# 07_eMMC.net
KiCad netlist of a schematic drawn in Altium Designer
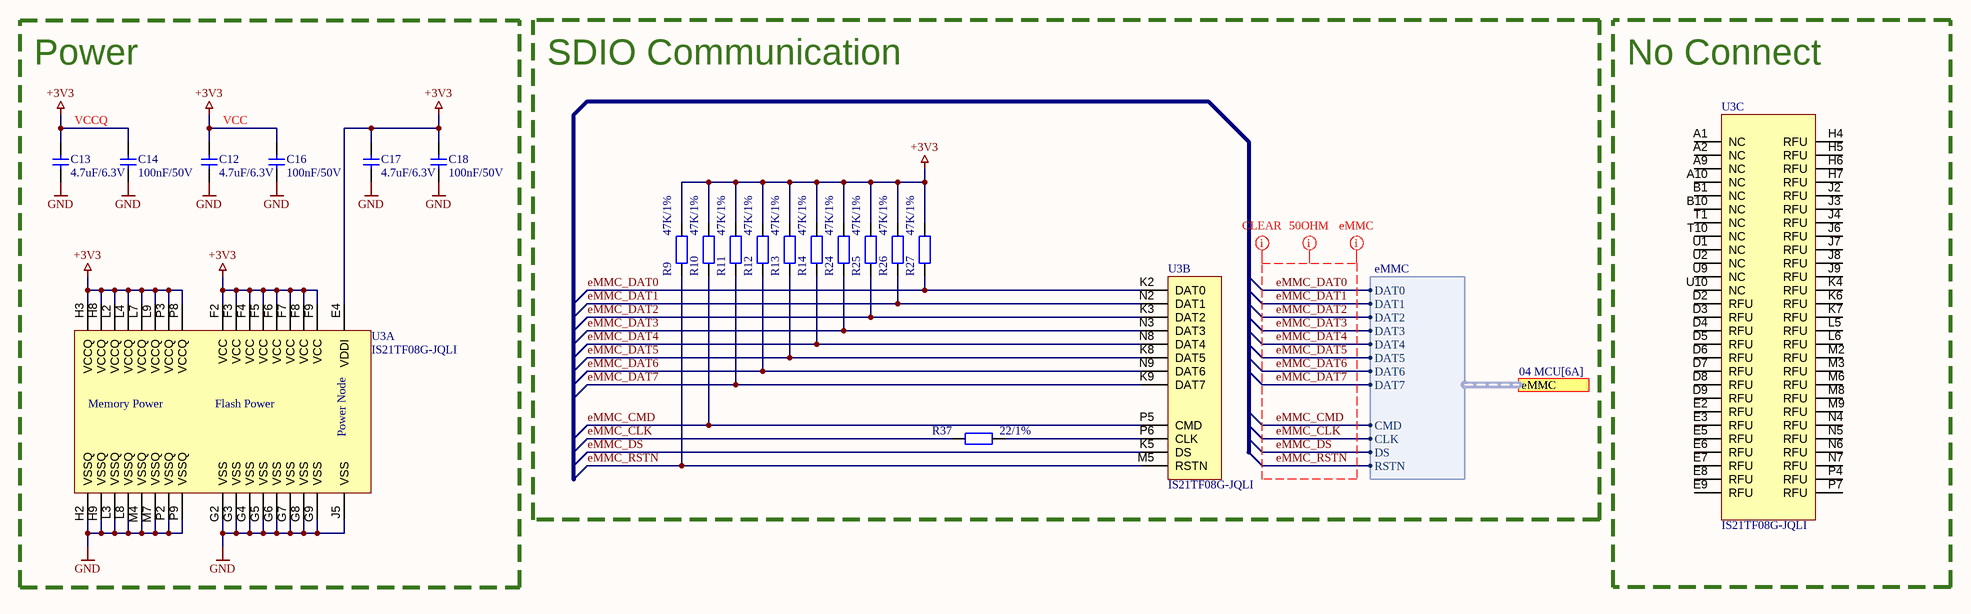
[diagram p0: 07 eMMC.SchDoc]

(export (version "E")
  (design (tool "Eeschema 10.0.6"))
  (components
    (comp (ref "C12")
      (value "4.7uF/6.3V")
      (footprint "CAPC1005X06M-0402")
      (description "4.7 µF ±20% 6.3V Ceramic Capacitor X5R 0402 (1005 Metric)")
      (fields (field (name "MPN") "GRM155R60J475ME47D"))
      (libsource (lib "Symbol") (part "GRM155R60J475ME47D"))
    )
    (comp (ref "C13")
      (value "4.7uF/6.3V")
      (footprint "CAPC1005X06M-0402")
      (description "4.7 µF ±20% 6.3V Ceramic Capacitor X5R 0402 (1005 Metric)")
      (fields (field (name "MPN") "GRM155R60J475ME47D"))
      (libsource (lib "Symbol") (part "GRM155R60J475ME47D"))
    )
    (comp (ref "C14")
      (value "100nF/50V")
      (footprint "CAPC1005X06M-0402")
      (description "0.1 µF ±10% 50V Ceramic Capacitor X7R 0402 (1005 Metric)")
      (fields (field (name "MPN") "GRM155R71H104KE14D"))
      (libsource (lib "Symbol") (part "GRM155R71H104KE14D"))
    )
    (comp (ref "C16")
      (value "100nF/50V")
      (footprint "CAPC1005X06M-0402")
      (description "0.1 µF ±10% 50V Ceramic Capacitor X7R 0402 (1005 Metric)")
      (fields (field (name "MPN") "GRM155R71H104KE14D"))
      (libsource (lib "Symbol") (part "GRM155R71H104KE14D"))
    )
    (comp (ref "C17")
      (value "4.7uF/6.3V")
      (footprint "CAPC1005X06M-0402")
      (description "4.7 µF ±20% 6.3V Ceramic Capacitor X5R 0402 (1005 Metric)")
      (fields (field (name "MPN") "GRM155R60J475ME47D"))
      (libsource (lib "Symbol") (part "GRM155R60J475ME47D"))
    )
    (comp (ref "C18")
      (value "100nF/50V")
      (footprint "CAPC1005X06M-0402")
      (description "0.1 µF ±10% 50V Ceramic Capacitor X7R 0402 (1005 Metric)")
      (fields (field (name "MPN") "GRM155R71H104KE14D"))
      (libsource (lib "Symbol") (part "GRM155R71H104KE14D"))
    )
    (comp (ref "R9")
      (value "47K/1%")
      (footprint "RESC1005X04M-0402")
      (description "47 kOhms ±1% 0.063W, 1/16W Chip Resistor 0402 (1005 Metric) Moisture Resistant Thick Film")
      (fields (field (name "MPN") "RC0402FR-0747KL"))
      (libsource (lib "Symbol") (part "RC0402FR-0747KL"))
    )
    (comp (ref "R10")
      (value "47K/1%")
      (footprint "RESC1005X04M-0402")
      (description "47 kOhms ±1% 0.063W, 1/16W Chip Resistor 0402 (1005 Metric) Moisture Resistant Thick Film")
      (fields (field (name "MPN") "RC0402FR-0747KL"))
      (libsource (lib "Symbol") (part "RC0402FR-0747KL"))
    )
    (comp (ref "R11")
      (value "47K/1%")
      (footprint "RESC1005X04M-0402")
      (description "47 kOhms ±1% 0.063W, 1/16W Chip Resistor 0402 (1005 Metric) Moisture Resistant Thick Film")
      (fields (field (name "MPN") "RC0402FR-0747KL"))
      (libsource (lib "Symbol") (part "RC0402FR-0747KL"))
    )
    (comp (ref "R12")
      (value "47K/1%")
      (footprint "RESC1005X04M-0402")
      (description "47 kOhms ±1% 0.063W, 1/16W Chip Resistor 0402 (1005 Metric) Moisture Resistant Thick Film")
      (fields (field (name "MPN") "RC0402FR-0747KL"))
      (libsource (lib "Symbol") (part "RC0402FR-0747KL"))
    )
    (comp (ref "R13")
      (value "47K/1%")
      (footprint "RESC1005X04M-0402")
      (description "47 kOhms ±1% 0.063W, 1/16W Chip Resistor 0402 (1005 Metric) Moisture Resistant Thick Film")
      (fields (field (name "MPN") "RC0402FR-0747KL"))
      (libsource (lib "Symbol") (part "RC0402FR-0747KL"))
    )
    (comp (ref "R14")
      (value "47K/1%")
      (footprint "RESC1005X04M-0402")
      (description "47 kOhms ±1% 0.063W, 1/16W Chip Resistor 0402 (1005 Metric) Moisture Resistant Thick Film")
      (fields (field (name "MPN") "RC0402FR-0747KL"))
      (libsource (lib "Symbol") (part "RC0402FR-0747KL"))
    )
    (comp (ref "R24")
      (value "47K/1%")
      (footprint "RESC1005X04M-0402")
      (description "47 kOhms ±1% 0.063W, 1/16W Chip Resistor 0402 (1005 Metric) Moisture Resistant Thick Film")
      (fields (field (name "MPN") "RC0402FR-0747KL"))
      (libsource (lib "Symbol") (part "RC0402FR-0747KL"))
    )
    (comp (ref "R25")
      (value "47K/1%")
      (footprint "RESC1005X04M-0402")
      (description "47 kOhms ±1% 0.063W, 1/16W Chip Resistor 0402 (1005 Metric) Moisture Resistant Thick Film")
      (fields (field (name "MPN") "RC0402FR-0747KL"))
      (libsource (lib "Symbol") (part "RC0402FR-0747KL"))
    )
    (comp (ref "R26")
      (value "47K/1%")
      (footprint "RESC1005X04M-0402")
      (description "47 kOhms ±1% 0.063W, 1/16W Chip Resistor 0402 (1005 Metric) Moisture Resistant Thick Film")
      (fields (field (name "MPN") "RC0402FR-0747KL"))
      (libsource (lib "Symbol") (part "RC0402FR-0747KL"))
    )
    (comp (ref "R27")
      (value "47K/1%")
      (footprint "RESC1005X04M-0402")
      (description "47 kOhms ±1% 0.063W, 1/16W Chip Resistor 0402 (1005 Metric) Moisture Resistant Thick Film")
      (fields (field (name "MPN") "RC0402FR-0747KL"))
      (libsource (lib "Symbol") (part "RC0402FR-0747KL"))
    )
    (comp (ref "R37")
      (value "22/1%")
      (footprint "RESC1005X04M-0402")
      (description "22 Ohms ±1% 0.063W, 1/16W Chip Resistor 0402 (1005 Metric) Moisture Resistant Thick Film")
      (fields (field (name "MPN") "RC0402FR-0722RL"))
      (libsource (lib "Symbol") (part "RC0402FR-0722RL"))
    )
    (comp (ref "U3")
      (value "IS21TF08G-JQLI")
      (footprint "BGA180C100P10X18_1400X1400X140")
      (description "FLASH - NAND (TLC) Memory IC 64Gbit MMC 200 MHz 100-LFBGA (14x18)")
      (libsource (lib "Symbol") (part "IS21TF08G-JQLI"))
    )
  )
  (nets
    (net (code "2") (name "+3V3") (class "Default")
      (node (ref "C12") (pin "2") (pinfunction "2_2") (pintype "passive"))
      (node (ref "C13") (pin "2") (pinfunction "2_2") (pintype "passive"))
      (node (ref "C14") (pin "2") (pinfunction "2_2") (pintype "passive"))
      (node (ref "C16") (pin "2") (pinfunction "2_2") (pintype "passive"))
      (node (ref "C17") (pin "2") (pinfunction "2_2") (pintype "passive"))
      (node (ref "C18") (pin "2") (pinfunction "2_2") (pintype "passive"))
      (node (ref "R10") (pin "2") (pinfunction "2_2") (pintype "passive"))
      (node (ref "R11") (pin "2") (pinfunction "2_2") (pintype "passive"))
      (node (ref "R12") (pin "2") (pinfunction "2_2") (pintype "passive"))
      (node (ref "R13") (pin "2") (pinfunction "2_2") (pintype "passive"))
      (node (ref "R14") (pin "2") (pinfunction "2_2") (pintype "passive"))
      (node (ref "R24") (pin "2") (pinfunction "2_2") (pintype "passive"))
      (node (ref "R25") (pin "2") (pinfunction "2_2") (pintype "passive"))
      (node (ref "R26") (pin "2") (pinfunction "2_2") (pintype "passive"))
      (node (ref "R27") (pin "2") (pinfunction "2_2") (pintype "passive"))
      (node (ref "R9") (pin "2") (pinfunction "2_2") (pintype "passive"))
      (node (ref "U3") (pin "E4") (pinfunction "VDDI_E4") (pintype "power_in"))
      (node (ref "U3") (pin "F2") (pinfunction "VCC_F2") (pintype "power_in"))
      (node (ref "U3") (pin "F3") (pinfunction "VCC_F3") (pintype "power_in"))
      (node (ref "U3") (pin "F4") (pinfunction "VCC_F4") (pintype "power_in"))
      (node (ref "U3") (pin "F5") (pinfunction "VCC_F5") (pintype "power_in"))
      (node (ref "U3") (pin "F6") (pinfunction "VCC_F6") (pintype "power_in"))
      (node (ref "U3") (pin "F7") (pinfunction "VCC_F7") (pintype "power_in"))
      (node (ref "U3") (pin "F8") (pinfunction "VCC_F8") (pintype "power_in"))
      (node (ref "U3") (pin "F9") (pinfunction "VCC_F9") (pintype "power_in"))
      (node (ref "U3") (pin "H3") (pinfunction "VCCQ_H3") (pintype "power_in"))
      (node (ref "U3") (pin "H8") (pinfunction "VCCQ_H8") (pintype "power_in"))
      (node (ref "U3") (pin "L2") (pinfunction "VCCQ_L2") (pintype "power_in"))
      (node (ref "U3") (pin "L4") (pinfunction "VCCQ_L4") (pintype "power_in"))
      (node (ref "U3") (pin "L7") (pinfunction "VCCQ_L7") (pintype "power_in"))
      (node (ref "U3") (pin "L9") (pinfunction "VCCQ_L9") (pintype "power_in"))
      (node (ref "U3") (pin "P3") (pinfunction "VCCQ_P3") (pintype "power_in"))
      (node (ref "U3") (pin "P8") (pinfunction "VCCQ_P8") (pintype "power_in"))
    )
    (net (code "3") (name "/eMMC_CLK") (class "Default")
      (node (ref "R37") (pin "1") (pinfunction "1_1") (pintype "passive"))
    )
    (net (code "4") (name "/eMMC_CMD") (class "Default")
      (node (ref "R10") (pin "1") (pinfunction "1_1") (pintype "passive"))
      (node (ref "U3") (pin "P5") (pinfunction "CMD_P5") (pintype "passive"))
    )
    (net (code "5") (name "/eMMC_DAT0") (class "Default")
      (node (ref "R27") (pin "1") (pinfunction "1_1") (pintype "passive"))
      (node (ref "U3") (pin "K2") (pinfunction "DAT0_K2") (pintype "passive"))
    )
    (net (code "6") (name "/eMMC_DAT1") (class "Default")
      (node (ref "R26") (pin "1") (pinfunction "1_1") (pintype "passive"))
      (node (ref "U3") (pin "N2") (pinfunction "DAT1_N2") (pintype "passive"))
    )
    (net (code "7") (name "/eMMC_DAT2") (class "Default")
      (node (ref "R25") (pin "1") (pinfunction "1_1") (pintype "passive"))
      (node (ref "U3") (pin "K3") (pinfunction "DAT2_K3") (pintype "passive"))
    )
    (net (code "8") (name "/eMMC_DAT3") (class "Default")
      (node (ref "R24") (pin "1") (pinfunction "1_1") (pintype "passive"))
      (node (ref "U3") (pin "N3") (pinfunction "DAT3_N3") (pintype "passive"))
    )
    (net (code "9") (name "/eMMC_DAT4") (class "Default")
      (node (ref "R14") (pin "1") (pinfunction "1_1") (pintype "passive"))
      (node (ref "U3") (pin "N8") (pinfunction "DAT4_N8") (pintype "passive"))
    )
    (net (code "10") (name "/eMMC_DAT5") (class "Default")
      (node (ref "R13") (pin "1") (pinfunction "1_1") (pintype "passive"))
      (node (ref "U3") (pin "K8") (pinfunction "DAT5_K8") (pintype "passive"))
    )
    (net (code "11") (name "/eMMC_DAT6") (class "Default")
      (node (ref "R12") (pin "1") (pinfunction "1_1") (pintype "passive"))
      (node (ref "U3") (pin "N9") (pinfunction "DAT6_N9") (pintype "passive"))
    )
    (net (code "12") (name "/eMMC_DAT7") (class "Default")
      (node (ref "R11") (pin "1") (pinfunction "1_1") (pintype "passive"))
      (node (ref "U3") (pin "K9") (pinfunction "DAT7_K9") (pintype "passive"))
    )
    (net (code "13") (name "/eMMC_DS") (class "Default")
      (node (ref "U3") (pin "K5") (pinfunction "DS_K5") (pintype "passive"))
    )
    (net (code "14") (name "/eMMC_RSTN") (class "Default")
      (node (ref "R9") (pin "1") (pinfunction "1_1") (pintype "passive"))
      (node (ref "U3") (pin "M5") (pinfunction "RSTN_M5") (pintype "passive"))
    )
    (net (code "16") (name "GND") (class "Default")
      (node (ref "C12") (pin "1") (pinfunction "1_1") (pintype "passive"))
      (node (ref "C13") (pin "1") (pinfunction "1_1") (pintype "passive"))
      (node (ref "C14") (pin "1") (pinfunction "1_1") (pintype "passive"))
      (node (ref "C16") (pin "1") (pinfunction "1_1") (pintype "passive"))
      (node (ref "C17") (pin "1") (pinfunction "1_1") (pintype "passive"))
      (node (ref "C18") (pin "1") (pinfunction "1_1") (pintype "passive"))
      (node (ref "U3") (pin "G2") (pinfunction "VSS_G2") (pintype "power_in"))
      (node (ref "U3") (pin "G3") (pinfunction "VSS_G3") (pintype "power_in"))
      (node (ref "U3") (pin "G4") (pinfunction "VSS_G4") (pintype "power_in"))
      (node (ref "U3") (pin "G5") (pinfunction "VSS_G5") (pintype "power_in"))
      (node (ref "U3") (pin "G6") (pinfunction "VSS_G6") (pintype "power_in"))
      (node (ref "U3") (pin "G7") (pinfunction "VSS_G7") (pintype "power_in"))
      (node (ref "U3") (pin "G8") (pinfunction "VSS_G8") (pintype "power_in"))
      (node (ref "U3") (pin "G9") (pinfunction "VSS_G9") (pintype "power_in"))
      (node (ref "U3") (pin "H2") (pinfunction "VSSQ_H2") (pintype "power_in"))
      (node (ref "U3") (pin "H9") (pinfunction "VSSQ_H9") (pintype "power_in"))
      (node (ref "U3") (pin "J5") (pinfunction "VSS_J5") (pintype "power_in"))
      (node (ref "U3") (pin "L3") (pinfunction "VSSQ_L3") (pintype "power_in"))
      (node (ref "U3") (pin "L8") (pinfunction "VSSQ_L8") (pintype "power_in"))
      (node (ref "U3") (pin "M4") (pinfunction "VSSQ_M4") (pintype "power_in"))
      (node (ref "U3") (pin "M7") (pinfunction "VSSQ_M7") (pintype "power_in"))
      (node (ref "U3") (pin "P2") (pinfunction "VSSQ_P2") (pintype "power_in"))
      (node (ref "U3") (pin "P9") (pinfunction "VSSQ_P9") (pintype "power_in"))
    )
    (net (code "17") (name "Net-(U3B-CLK)") (class "Default")
      (node (ref "R37") (pin "2") (pinfunction "2_2") (pintype "passive"))
      (node (ref "U3") (pin "P6") (pinfunction "CLK_P6") (pintype "passive"))
    )
    (net (code "18") (name "unconnected-(U3C-NC-PadA1)") (class "Default")
      (node (ref "U3") (pin "A1") (pinfunction "NC_A1") (pintype "passive"))
    )
    (net (code "19") (name "unconnected-(U3C-NC-PadA2)") (class "Default")
      (node (ref "U3") (pin "A2") (pinfunction "NC_A2") (pintype "passive"))
    )
    (net (code "20") (name "unconnected-(U3C-NC-PadA9)") (class "Default")
      (node (ref "U3") (pin "A9") (pinfunction "NC_A9") (pintype "passive"))
    )
    (net (code "21") (name "unconnected-(U3C-NC-PadA10)") (class "Default")
      (node (ref "U3") (pin "A10") (pinfunction "NC_A10") (pintype "passive"))
    )
    (net (code "22") (name "unconnected-(U3C-NC-PadB1)") (class "Default")
      (node (ref "U3") (pin "B1") (pinfunction "NC_B1") (pintype "passive"))
    )
    (net (code "23") (name "unconnected-(U3C-NC-PadB10)") (class "Default")
      (node (ref "U3") (pin "B10") (pinfunction "NC_B10") (pintype "passive"))
    )
    (net (code "24") (name "unconnected-(U3C-NC-PadT1)") (class "Default")
      (node (ref "U3") (pin "T1") (pinfunction "NC_T1") (pintype "passive"))
    )
    (net (code "25") (name "unconnected-(U3C-NC-PadT10)") (class "Default")
      (node (ref "U3") (pin "T10") (pinfunction "NC_T10") (pintype "passive"))
    )
    (net (code "26") (name "unconnected-(U3C-NC-PadU1)") (class "Default")
      (node (ref "U3") (pin "U1") (pinfunction "NC_U1") (pintype "passive"))
    )
    (net (code "27") (name "unconnected-(U3C-NC-PadU2)") (class "Default")
      (node (ref "U3") (pin "U2") (pinfunction "NC_U2") (pintype "passive"))
    )
    (net (code "28") (name "unconnected-(U3C-NC-PadU9)") (class "Default")
      (node (ref "U3") (pin "U9") (pinfunction "NC_U9") (pintype "passive"))
    )
    (net (code "29") (name "unconnected-(U3C-NC-PadU10)") (class "Default")
      (node (ref "U3") (pin "U10") (pinfunction "NC_U10") (pintype "passive"))
    )
    (net (code "30") (name "unconnected-(U3C-RFU-PadD2)") (class "Default")
      (node (ref "U3") (pin "D2") (pinfunction "RFU_D2") (pintype "passive"))
    )
    (net (code "31") (name "unconnected-(U3C-RFU-PadD3)") (class "Default")
      (node (ref "U3") (pin "D3") (pinfunction "RFU_D3") (pintype "passive"))
    )
    (net (code "32") (name "unconnected-(U3C-RFU-PadD4)") (class "Default")
      (node (ref "U3") (pin "D4") (pinfunction "RFU_D4") (pintype "passive"))
    )
    (net (code "33") (name "unconnected-(U3C-RFU-PadD5)") (class "Default")
      (node (ref "U3") (pin "D5") (pinfunction "RFU_D5") (pintype "passive"))
    )
    (net (code "34") (name "unconnected-(U3C-RFU-PadD6)") (class "Default")
      (node (ref "U3") (pin "D6") (pinfunction "RFU_D6") (pintype "passive"))
    )
    (net (code "35") (name "unconnected-(U3C-RFU-PadD7)") (class "Default")
      (node (ref "U3") (pin "D7") (pinfunction "RFU_D7") (pintype "passive"))
    )
    (net (code "36") (name "unconnected-(U3C-RFU-PadD8)") (class "Default")
      (node (ref "U3") (pin "D8") (pinfunction "RFU_D8") (pintype "passive"))
    )
    (net (code "37") (name "unconnected-(U3C-RFU-PadD9)") (class "Default")
      (node (ref "U3") (pin "D9") (pinfunction "RFU_D9") (pintype "passive"))
    )
    (net (code "38") (name "unconnected-(U3C-RFU-PadE2)") (class "Default")
      (node (ref "U3") (pin "E2") (pinfunction "RFU_E2") (pintype "passive"))
    )
    (net (code "39") (name "unconnected-(U3C-RFU-PadE3)") (class "Default")
      (node (ref "U3") (pin "E3") (pinfunction "RFU_E3") (pintype "passive"))
    )
    (net (code "40") (name "unconnected-(U3C-RFU-PadE5)") (class "Default")
      (node (ref "U3") (pin "E5") (pinfunction "RFU_E5") (pintype "passive"))
    )
    (net (code "41") (name "unconnected-(U3C-RFU-PadE6)") (class "Default")
      (node (ref "U3") (pin "E6") (pinfunction "RFU_E6") (pintype "passive"))
    )
    (net (code "42") (name "unconnected-(U3C-RFU-PadE7)") (class "Default")
      (node (ref "U3") (pin "E7") (pinfunction "RFU_E7") (pintype "passive"))
    )
    (net (code "43") (name "unconnected-(U3C-RFU-PadE8)") (class "Default")
      (node (ref "U3") (pin "E8") (pinfunction "RFU_E8") (pintype "passive"))
    )
    (net (code "44") (name "unconnected-(U3C-RFU-PadE9)") (class "Default")
      (node (ref "U3") (pin "E9") (pinfunction "RFU_E9") (pintype "passive"))
    )
    (net (code "45") (name "unconnected-(U3C-RFU-PadH4)") (class "Default")
      (node (ref "U3") (pin "H4") (pinfunction "RFU_H4") (pintype "passive"))
    )
    (net (code "46") (name "unconnected-(U3C-RFU-PadH5)") (class "Default")
      (node (ref "U3") (pin "H5") (pinfunction "RFU_H5") (pintype "passive"))
    )
    (net (code "47") (name "unconnected-(U3C-RFU-PadH6)") (class "Default")
      (node (ref "U3") (pin "H6") (pinfunction "RFU_H6") (pintype "passive"))
    )
    (net (code "48") (name "unconnected-(U3C-RFU-PadH7)") (class "Default")
      (node (ref "U3") (pin "H7") (pinfunction "RFU_H7") (pintype "passive"))
    )
    (net (code "49") (name "unconnected-(U3C-RFU-PadJ2)") (class "Default")
      (node (ref "U3") (pin "J2") (pinfunction "RFU_J2") (pintype "passive"))
    )
    (net (code "50") (name "unconnected-(U3C-RFU-PadJ3)") (class "Default")
      (node (ref "U3") (pin "J3") (pinfunction "RFU_J3") (pintype "passive"))
    )
    (net (code "51") (name "unconnected-(U3C-RFU-PadJ4)") (class "Default")
      (node (ref "U3") (pin "J4") (pinfunction "RFU_J4") (pintype "passive"))
    )
    (net (code "52") (name "unconnected-(U3C-RFU-PadJ6)") (class "Default")
      (node (ref "U3") (pin "J6") (pinfunction "RFU_J6") (pintype "passive"))
    )
    (net (code "53") (name "unconnected-(U3C-RFU-PadJ7)") (class "Default")
      (node (ref "U3") (pin "J7") (pinfunction "RFU_J7") (pintype "passive"))
    )
    (net (code "54") (name "unconnected-(U3C-RFU-PadJ8)") (class "Default")
      (node (ref "U3") (pin "J8") (pinfunction "RFU_J8") (pintype "passive"))
    )
    (net (code "55") (name "unconnected-(U3C-RFU-PadJ9)") (class "Default")
      (node (ref "U3") (pin "J9") (pinfunction "RFU_J9") (pintype "passive"))
    )
    (net (code "56") (name "unconnected-(U3C-RFU-PadK4)") (class "Default")
      (node (ref "U3") (pin "K4") (pinfunction "RFU_K4") (pintype "passive"))
    )
    (net (code "57") (name "unconnected-(U3C-RFU-PadK6)") (class "Default")
      (node (ref "U3") (pin "K6") (pinfunction "RFU_K6") (pintype "passive"))
    )
    (net (code "58") (name "unconnected-(U3C-RFU-PadK7)") (class "Default")
      (node (ref "U3") (pin "K7") (pinfunction "RFU_K7") (pintype "passive"))
    )
    (net (code "59") (name "unconnected-(U3C-RFU-PadL5)") (class "Default")
      (node (ref "U3") (pin "L5") (pinfunction "RFU_L5") (pintype "passive"))
    )
    (net (code "60") (name "unconnected-(U3C-RFU-PadL6)") (class "Default")
      (node (ref "U3") (pin "L6") (pinfunction "RFU_L6") (pintype "passive"))
    )
    (net (code "61") (name "unconnected-(U3C-RFU-PadM2)") (class "Default")
      (node (ref "U3") (pin "M2") (pinfunction "RFU_M2") (pintype "passive"))
    )
    (net (code "62") (name "unconnected-(U3C-RFU-PadM3)") (class "Default")
      (node (ref "U3") (pin "M3") (pinfunction "RFU_M3") (pintype "passive"))
    )
    (net (code "63") (name "unconnected-(U3C-RFU-PadM6)") (class "Default")
      (node (ref "U3") (pin "M6") (pinfunction "RFU_M6") (pintype "passive"))
    )
    (net (code "64") (name "unconnected-(U3C-RFU-PadM8)") (class "Default")
      (node (ref "U3") (pin "M8") (pinfunction "RFU_M8") (pintype "passive"))
    )
    (net (code "65") (name "unconnected-(U3C-RFU-PadM9)") (class "Default")
      (node (ref "U3") (pin "M9") (pinfunction "RFU_M9") (pintype "passive"))
    )
    (net (code "66") (name "unconnected-(U3C-RFU-PadN4)") (class "Default")
      (node (ref "U3") (pin "N4") (pinfunction "RFU_N4") (pintype "passive"))
    )
    (net (code "67") (name "unconnected-(U3C-RFU-PadN5)") (class "Default")
      (node (ref "U3") (pin "N5") (pinfunction "RFU_N5") (pintype "passive"))
    )
    (net (code "68") (name "unconnected-(U3C-RFU-PadN6)") (class "Default")
      (node (ref "U3") (pin "N6") (pinfunction "RFU_N6") (pintype "passive"))
    )
    (net (code "69") (name "unconnected-(U3C-RFU-PadN7)") (class "Default")
      (node (ref "U3") (pin "N7") (pinfunction "RFU_N7") (pintype "passive"))
    )
    (net (code "70") (name "unconnected-(U3C-RFU-PadP4)") (class "Default")
      (node (ref "U3") (pin "P4") (pinfunction "RFU_P4") (pintype "passive"))
    )
    (net (code "71") (name "unconnected-(U3C-RFU-PadP7)") (class "Default")
      (node (ref "U3") (pin "P7") (pinfunction "RFU_P7") (pintype "passive"))
    )
  )
)
